# BTT_toolhead_expansion.net
KiCad netlist of a schematic drawn in Altium Designer
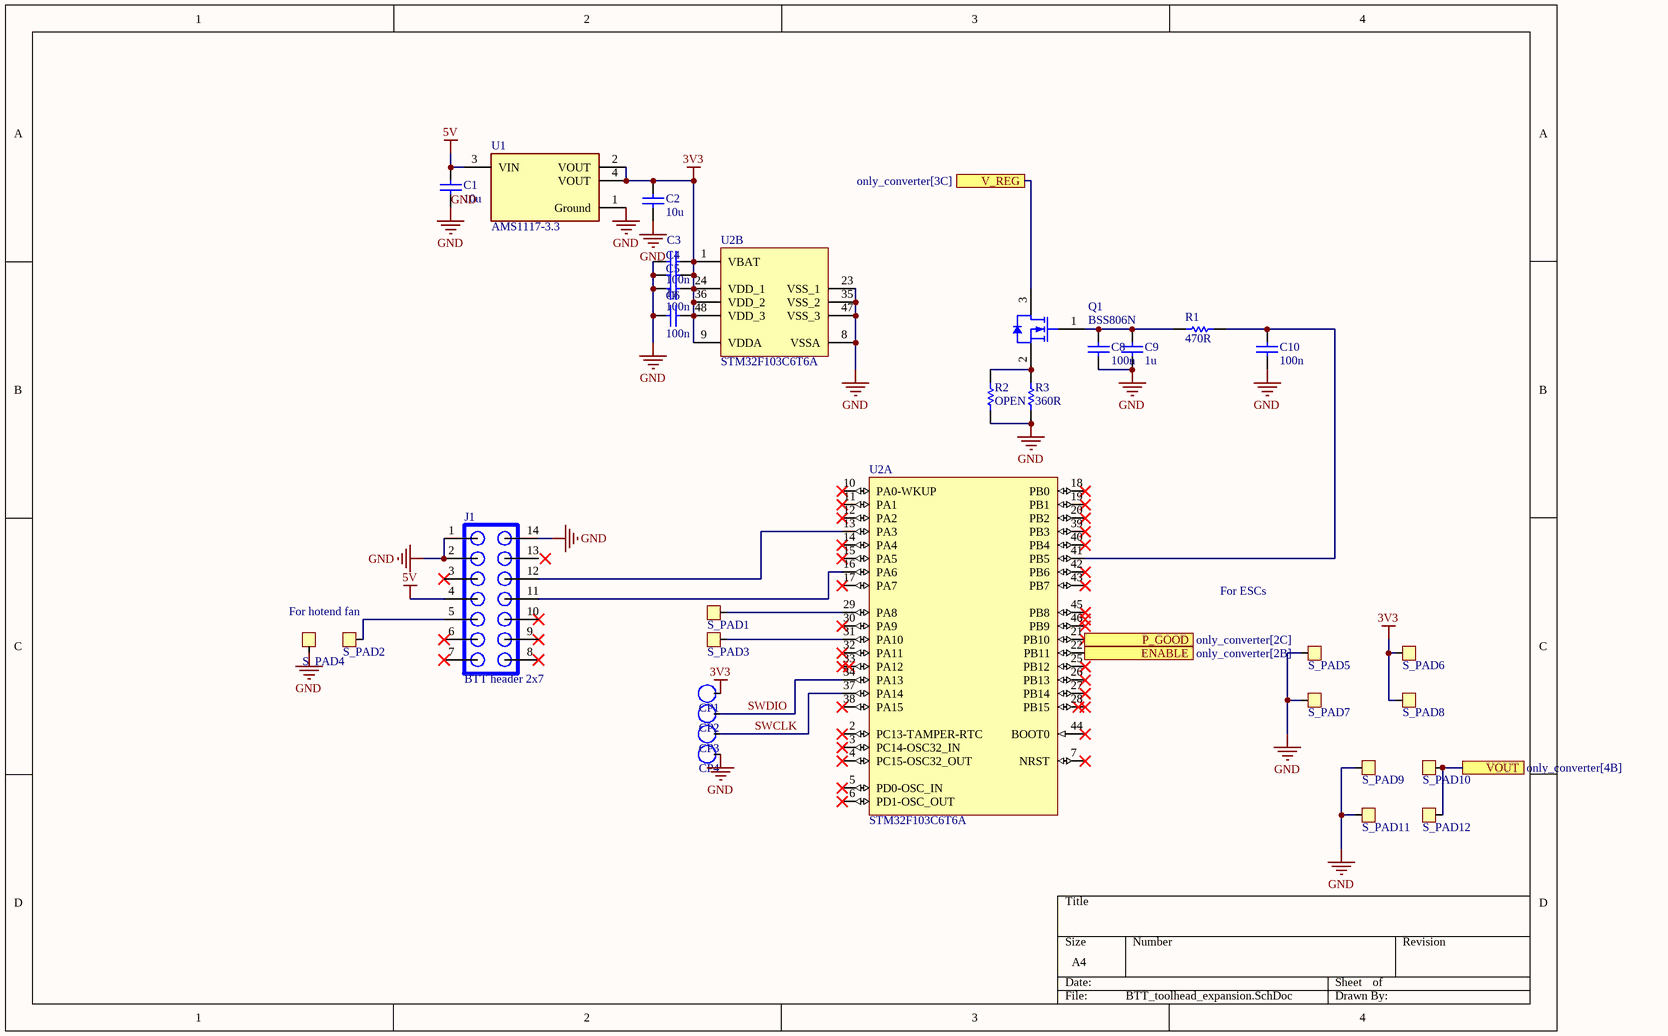
[diagram p0: BTT_toolhead_expansion.SchDoc]

(export (version "E")
  (design (tool "Eeschema 10.0.6"))
  (components
    (comp (ref "C1")
      (value "10u")
      (footprint "CAP FILM 0603_1608")
      (description "Capacitor")
      (libsource (lib "Simulation Generic Components") (part "Capacitor"))
    )
    (comp (ref "C2")
      (value "10u")
      (footprint "CAP FILM 0603_1608")
      (description "Capacitor")
      (libsource (lib "Simulation Generic Components") (part "Capacitor"))
    )
    (comp (ref "C3")
      (value "100n")
      (footprint "CAP FILM 0603_1608")
      (description "Capacitor")
      (libsource (lib "Simulation Generic Components") (part "Capacitor"))
    )
    (comp (ref "C4")
      (value "1p")
      (footprint "CAP FILM 0603_1608")
      (description "Capacitor")
      (libsource (lib "Simulation Generic Components") (part "Capacitor"))
    )
    (comp (ref "C5")
      (value "100n")
      (footprint "CAP FILM 0603_1608")
      (description "Capacitor")
      (libsource (lib "Simulation Generic Components") (part "Capacitor"))
    )
    (comp (ref "C6")
      (value "100n")
      (footprint "CAP FILM 0603_1608")
      (description "Capacitor")
      (libsource (lib "Simulation Generic Components") (part "Capacitor"))
    )
    (comp (ref "C8")
      (value "100n")
      (footprint "CAP FILM 0603_1608")
      (description "Capacitor")
      (libsource (lib "Simulation Generic Components") (part "Capacitor"))
    )
    (comp (ref "C9")
      (value "1u")
      (footprint "CAP FILM 0603_1608")
      (description "Capacitor")
      (libsource (lib "Simulation Generic Components") (part "Capacitor"))
    )
    (comp (ref "C10")
      (value "100n")
      (footprint "CAP FILM 0603_1608")
      (description "Capacitor")
      (libsource (lib "Simulation Generic Components") (part "Capacitor"))
    )
    (comp (ref "CP1")
      (value "CONNECT_PAD")
      (footprint "ROUND_SMALL")
      (libsource (lib "solderpad") (part "CONNECT_PAD"))
    )
    (comp (ref "CP2")
      (value "CONNECT_PAD")
      (footprint "ROUND_SMALL")
      (libsource (lib "solderpad") (part "CONNECT_PAD"))
    )
    (comp (ref "CP3")
      (value "CONNECT_PAD")
      (footprint "ROUND_SMALL")
      (libsource (lib "solderpad") (part "CONNECT_PAD"))
    )
    (comp (ref "CP4")
      (value "CONNECT_PAD")
      (footprint "ROUND_SMALL")
      (libsource (lib "solderpad") (part "CONNECT_PAD"))
    )
    (comp (ref "J1")
      (value "BTT header 2x7")
      (footprint "BTT connector 2x7 THT")
      (libsource (lib "BTT_connector") (part "BTT header 2x7"))
    )
    (comp (ref "Q1")
      (value "BSS806N")
      (footprint "INF-PG-SOT23_M")
      (fields (field (name "MANUFACTURER") "Infineon"))
      (libsource (lib "Altium Content Vault") (part "INF-NEMOS-GSD-3"))
    )
    (comp (ref "R1")
      (value "470R")
      (footprint "RES 0603_1608")
      (description "Resistor")
      (libsource (lib "Simulation Generic Components") (part "Resistor"))
    )
    (comp (ref "R2")
      (value "OPEN")
      (footprint "RES 0603_1608")
      (description "Resistor")
      (libsource (lib "Simulation Generic Components") (part "Resistor"))
    )
    (comp (ref "R3")
      (value "360R")
      (footprint "RES 0603_1608")
      (description "Resistor")
      (libsource (lib "Simulation Generic Components") (part "Resistor"))
    )
    (comp (ref "S_PAD1")
      (value "SOLDER_PAD")
      (footprint "PAD_SQUARE")
      (libsource (lib "solderpad") (part "SOLDER_PAD"))
    )
    (comp (ref "S_PAD2")
      (value "SOLDER_PAD")
      (footprint "PAD_SQUARE")
      (libsource (lib "solderpad") (part "SOLDER_PAD"))
    )
    (comp (ref "S_PAD3")
      (value "SOLDER_PAD")
      (footprint "PAD_SQUARE")
      (libsource (lib "") (part "SOLDER_PAD_3"))
    )
    (comp (ref "S_PAD4")
      (value "SOLDER_PAD")
      (footprint "PAD_SQUARE")
      (libsource (lib "") (part "SOLDER_PAD_2"))
    )
    (comp (ref "S_PAD5")
      (value "SOLDER_PAD")
      (footprint "PAD_SQUARE")
      (libsource (lib "") (part "SOLDER_PAD_1"))
    )
    (comp (ref "S_PAD6")
      (value "SOLDER_PAD")
      (footprint "PAD_SQUARE")
      (libsource (lib "") (part "SOLDER_PAD_1"))
    )
    (comp (ref "S_PAD7")
      (value "SOLDER_PAD")
      (footprint "PAD_SQUARE")
      (libsource (lib "") (part "SOLDER_PAD_1"))
    )
    (comp (ref "S_PAD8")
      (value "SOLDER_PAD")
      (footprint "PAD_SQUARE")
      (libsource (lib "") (part "SOLDER_PAD_1"))
    )
    (comp (ref "S_PAD9")
      (value "SOLDER_PAD")
      (footprint "PAD_SQUARE")
      (libsource (lib "") (part "SOLDER_PAD_1"))
    )
    (comp (ref "S_PAD10")
      (value "SOLDER_PAD")
      (footprint "PAD_SQUARE")
      (libsource (lib "") (part "SOLDER_PAD_3"))
    )
    (comp (ref "S_PAD11")
      (value "SOLDER_PAD")
      (footprint "PAD_SQUARE")
      (libsource (lib "") (part "SOLDER_PAD_1"))
    )
    (comp (ref "S_PAD12")
      (value "SOLDER_PAD")
      (footprint "PAD_SQUARE")
      (libsource (lib "") (part "SOLDER_PAD_3"))
    )
    (comp (ref "U1")
      (value "AMS1117-3.3")
      (footprint "FP-AMS1117-IPC_C")
      (description "LDO Voltage Regulators 1A, 3.3V")
      (fields
        (field (name "OCTOPART") "https://octopart.com/ams1117-3.3-advanced+monolithic+systems-25899300")
        (field (name "MANUFACTURER") "Advanced Monolithic Systems")
      )
      (libsource (lib "Altium Content Vault") (part "8bdbb5f8e77002000e30dd2845d0354"))
    )
    (comp (ref "U2")
      (value "STM32F103C6T6A")
      (footprint "STM-LQFP48_M")
      (libsource (lib "Altium Content Vault") (part "MC-ARM-STM32F103X4_6-SQ48"))
    )
  )
  (nets
    (net (code "1") (name "/ENABLE") (class "Default")
      (node (ref "U2") (pin "22") (pinfunction "PB11_22") (pintype "bidirectional"))
    )
    (net (code "2") (name "/P_GOOD") (class "Default")
      (node (ref "U2") (pin "21") (pinfunction "PB10_21") (pintype "bidirectional+no_connect"))
    )
    (net (code "3") (name "/SWCLK") (class "Default")
      (node (ref "CP3") (pin "1") (pinfunction "1_1") (pintype "passive"))
      (node (ref "U2") (pin "37") (pinfunction "PA14_37") (pintype "bidirectional"))
    )
    (net (code "4") (name "/SWDIO") (class "Default")
      (node (ref "CP2") (pin "1") (pinfunction "1_1") (pintype "passive"))
      (node (ref "U2") (pin "34") (pinfunction "PA13_34") (pintype "bidirectional"))
    )
    (net (code "5") (name "/VOUT") (class "Default")
      (node (ref "S_PAD10") (pin "1") (pinfunction "0_1") (pintype "passive"))
      (node (ref "S_PAD12") (pin "1") (pinfunction "0_1") (pintype "passive"))
    )
    (net (code "6") (name "/V_REG") (class "Default")
      (node (ref "Q1") (pin "3") (pinfunction "DRAIN_3") (pintype "passive"))
    )
    (net (code "7") (name "3V3") (class "Default")
      (node (ref "C2") (pin "2") (pinfunction "2_2") (pintype "passive"))
      (node (ref "C3") (pin "1") (pinfunction "1_1") (pintype "passive"))
      (node (ref "C4") (pin "1") (pinfunction "1_1") (pintype "passive"))
      (node (ref "C5") (pin "1") (pinfunction "1_1") (pintype "passive"))
      (node (ref "C6") (pin "1") (pinfunction "1_1") (pintype "passive"))
      (node (ref "CP1") (pin "1") (pinfunction "1_1") (pintype "passive"))
      (node (ref "S_PAD6") (pin "1") (pinfunction "0_1") (pintype "passive"))
      (node (ref "S_PAD8") (pin "1") (pinfunction "0_1") (pintype "passive"))
      (node (ref "U1") (pin "2") (pinfunction "VOUT_2") (pintype "passive"))
      (node (ref "U1") (pin "4") (pinfunction "VOUT_4") (pintype "passive"))
      (node (ref "U2") (pin "1") (pinfunction "VBAT_1") (pintype "power_in"))
      (node (ref "U2") (pin "24") (pinfunction "VDD_1_24") (pintype "power_in"))
      (node (ref "U2") (pin "36") (pinfunction "VDD_2_36") (pintype "power_in"))
      (node (ref "U2") (pin "48") (pinfunction "VDD_3_48") (pintype "power_in"))
      (node (ref "U2") (pin "9") (pinfunction "VDDA_9") (pintype "power_in"))
    )
    (net (code "8") (name "5V") (class "Default")
      (node (ref "C1") (pin "2") (pinfunction "2_2") (pintype "passive"))
      (node (ref "J1") (pin "4") (pinfunction "4_4") (pintype "passive"))
      (node (ref "U1") (pin "3") (pinfunction "VIN_3") (pintype "power_in"))
    )
    (net (code "9") (name "GND") (class "Default")
      (node (ref "C1") (pin "1") (pinfunction "1_1") (pintype "passive"))
      (node (ref "C10") (pin "1") (pinfunction "1_1") (pintype "passive"))
      (node (ref "C2") (pin "1") (pinfunction "1_1") (pintype "passive"))
      (node (ref "C3") (pin "2") (pinfunction "2_2") (pintype "passive"))
      (node (ref "C4") (pin "2") (pinfunction "2_2") (pintype "passive"))
      (node (ref "C5") (pin "2") (pinfunction "2_2") (pintype "passive"))
      (node (ref "C6") (pin "2") (pinfunction "2_2") (pintype "passive"))
      (node (ref "C8") (pin "1") (pinfunction "1_1") (pintype "passive"))
      (node (ref "C9") (pin "1") (pinfunction "1_1") (pintype "passive"))
      (node (ref "CP4") (pin "1") (pinfunction "1_1") (pintype "passive"))
      (node (ref "J1") (pin "1") (pinfunction "1_1") (pintype "passive"))
      (node (ref "J1") (pin "14") (pinfunction "14_14") (pintype "passive"))
      (node (ref "J1") (pin "2") (pinfunction "2_2") (pintype "passive"))
      (node (ref "R2") (pin "1") (pinfunction "1_1") (pintype "passive"))
      (node (ref "R3") (pin "1") (pinfunction "1_1") (pintype "passive"))
      (node (ref "S_PAD11") (pin "1") (pinfunction "0_1") (pintype "passive"))
      (node (ref "S_PAD4") (pin "1") (pinfunction "0_1") (pintype "passive"))
      (node (ref "S_PAD5") (pin "1") (pinfunction "0_1") (pintype "passive"))
      (node (ref "S_PAD7") (pin "1") (pinfunction "0_1") (pintype "passive"))
      (node (ref "S_PAD9") (pin "1") (pinfunction "0_1") (pintype "passive"))
      (node (ref "U1") (pin "1") (pinfunction "Ground_1") (pintype "power_in"))
      (node (ref "U2") (pin "23") (pinfunction "VSS_1_23") (pintype "power_in"))
      (node (ref "U2") (pin "35") (pinfunction "VSS_2_35") (pintype "power_in"))
      (node (ref "U2") (pin "47") (pinfunction "VSS_3_47") (pintype "power_in"))
      (node (ref "U2") (pin "8") (pinfunction "VSSA_8") (pintype "power_in"))
    )
    (net (code "10") (name "Net-(Q1-GATE)") (class "Default")
      (node (ref "C8") (pin "2") (pinfunction "2_2") (pintype "passive"))
      (node (ref "C9") (pin "2") (pinfunction "2_2") (pintype "passive"))
      (node (ref "Q1") (pin "1") (pinfunction "GATE_1") (pintype "passive"))
      (node (ref "R1") (pin "1") (pinfunction "1_1") (pintype "passive"))
    )
    (net (code "11") (name "Net-(Q1-SOURCE)") (class "Default")
      (node (ref "Q1") (pin "2") (pinfunction "SOURCE_2") (pintype "passive"))
      (node (ref "R2") (pin "2") (pinfunction "2_2") (pintype "passive"))
      (node (ref "R3") (pin "2") (pinfunction "2_2") (pintype "passive"))
    )
    (net (code "12") (name "Net-(S_PAD1-0)") (class "Default")
      (node (ref "S_PAD1") (pin "1") (pinfunction "0_1") (pintype "passive"))
      (node (ref "U2") (pin "29") (pinfunction "PA8_29") (pintype "bidirectional"))
    )
    (net (code "13") (name "Net-(S_PAD2-0)") (class "Default")
      (node (ref "J1") (pin "5") (pinfunction "5_5") (pintype "passive"))
      (node (ref "S_PAD2") (pin "1") (pinfunction "0_1") (pintype "passive"))
    )
    (net (code "14") (name "Net-(S_PAD3-0)") (class "Default")
      (node (ref "S_PAD3") (pin "1") (pinfunction "0_1") (pintype "passive"))
      (node (ref "U2") (pin "31") (pinfunction "PA10_31") (pintype "bidirectional"))
    )
    (net (code "15") (name "Net-(U2A-PA3)") (class "Default")
      (node (ref "J1") (pin "12") (pinfunction "12_12") (pintype "passive"))
      (node (ref "U2") (pin "13") (pinfunction "PA3_13") (pintype "bidirectional"))
    )
    (net (code "16") (name "Net-(U2A-PA6)") (class "Default")
      (node (ref "J1") (pin "11") (pinfunction "11_11") (pintype "passive"))
      (node (ref "U2") (pin "16") (pinfunction "PA6_16") (pintype "bidirectional"))
    )
    (net (code "17") (name "Net-(U2A-PB5)") (class "Default")
      (node (ref "C10") (pin "2") (pinfunction "2_2") (pintype "passive"))
      (node (ref "R1") (pin "2") (pinfunction "2_2") (pintype "passive"))
      (node (ref "U2") (pin "41") (pinfunction "PB5_41") (pintype "bidirectional"))
    )
    (net (code "18") (name "unconnected-(J1-Pad3)") (class "Default")
      (node (ref "J1") (pin "3") (pinfunction "3_3") (pintype "passive+no_connect"))
    )
    (net (code "19") (name "unconnected-(J1-Pad6)") (class "Default")
      (node (ref "J1") (pin "6") (pinfunction "6_6") (pintype "passive+no_connect"))
    )
    (net (code "20") (name "unconnected-(J1-Pad7)") (class "Default")
      (node (ref "J1") (pin "7") (pinfunction "7_7") (pintype "passive+no_connect"))
    )
    (net (code "21") (name "unconnected-(J1-Pad8)") (class "Default")
      (node (ref "J1") (pin "8") (pinfunction "8_8") (pintype "passive+no_connect"))
    )
    (net (code "22") (name "unconnected-(J1-Pad9)") (class "Default")
      (node (ref "J1") (pin "9") (pinfunction "9_9") (pintype "passive+no_connect"))
    )
    (net (code "23") (name "unconnected-(J1-Pad10)") (class "Default")
      (node (ref "J1") (pin "10") (pinfunction "10_10") (pintype "passive+no_connect"))
    )
    (net (code "24") (name "unconnected-(J1-Pad13)") (class "Default")
      (node (ref "J1") (pin "13") (pinfunction "13_13") (pintype "passive"))
    )
    (net (code "25") (name "unconnected-(U2A-BOOT0-Pad44)") (class "Default")
      (node (ref "U2") (pin "44") (pinfunction "BOOT0_44") (pintype "input+no_connect"))
    )
    (net (code "26") (name "unconnected-(U2A-NRST-Pad7)") (class "Default")
      (node (ref "U2") (pin "7") (pinfunction "NRST_7") (pintype "bidirectional+no_connect"))
    )
    (net (code "27") (name "unconnected-(U2A-PA0-WKUP-Pad10)") (class "Default")
      (node (ref "U2") (pin "10") (pinfunction "PA0-WKUP_10") (pintype "bidirectional+no_connect"))
    )
    (net (code "28") (name "unconnected-(U2A-PA1-Pad11)") (class "Default")
      (node (ref "U2") (pin "11") (pinfunction "PA1_11") (pintype "bidirectional+no_connect"))
    )
    (net (code "29") (name "unconnected-(U2A-PA2-Pad12)") (class "Default")
      (node (ref "U2") (pin "12") (pinfunction "PA2_12") (pintype "bidirectional+no_connect"))
    )
    (net (code "30") (name "unconnected-(U2A-PA4-Pad14)") (class "Default")
      (node (ref "U2") (pin "14") (pinfunction "PA4_14") (pintype "bidirectional+no_connect"))
    )
    (net (code "31") (name "unconnected-(U2A-PA5-Pad15)") (class "Default")
      (node (ref "U2") (pin "15") (pinfunction "PA5_15") (pintype "bidirectional+no_connect"))
    )
    (net (code "32") (name "unconnected-(U2A-PA7-Pad17)") (class "Default")
      (node (ref "U2") (pin "17") (pinfunction "PA7_17") (pintype "bidirectional+no_connect"))
    )
    (net (code "33") (name "unconnected-(U2A-PA9-Pad30)") (class "Default")
      (node (ref "U2") (pin "30") (pinfunction "PA9_30") (pintype "bidirectional+no_connect"))
    )
    (net (code "34") (name "unconnected-(U2A-PA11-Pad32)") (class "Default")
      (node (ref "U2") (pin "32") (pinfunction "PA11_32") (pintype "bidirectional+no_connect"))
    )
    (net (code "35") (name "unconnected-(U2A-PA12-Pad33)") (class "Default")
      (node (ref "U2") (pin "33") (pinfunction "PA12_33") (pintype "bidirectional+no_connect"))
    )
    (net (code "36") (name "unconnected-(U2A-PA15-Pad38)") (class "Default")
      (node (ref "U2") (pin "38") (pinfunction "PA15_38") (pintype "bidirectional+no_connect"))
    )
    (net (code "37") (name "unconnected-(U2A-PB0-Pad18)") (class "Default")
      (node (ref "U2") (pin "18") (pinfunction "PB0_18") (pintype "bidirectional+no_connect"))
    )
    (net (code "38") (name "unconnected-(U2A-PB1-Pad19)") (class "Default")
      (node (ref "U2") (pin "19") (pinfunction "PB1_19") (pintype "bidirectional+no_connect"))
    )
    (net (code "39") (name "unconnected-(U2A-PB2-Pad20)") (class "Default")
      (node (ref "U2") (pin "20") (pinfunction "PB2_20") (pintype "bidirectional+no_connect"))
    )
    (net (code "40") (name "unconnected-(U2A-PB3-Pad39)") (class "Default")
      (node (ref "U2") (pin "39") (pinfunction "PB3_39") (pintype "bidirectional+no_connect"))
    )
    (net (code "41") (name "unconnected-(U2A-PB4-Pad40)") (class "Default")
      (node (ref "U2") (pin "40") (pinfunction "PB4_40") (pintype "bidirectional+no_connect"))
    )
    (net (code "42") (name "unconnected-(U2A-PB6-Pad42)") (class "Default")
      (node (ref "U2") (pin "42") (pinfunction "PB6_42") (pintype "bidirectional+no_connect"))
    )
    (net (code "43") (name "unconnected-(U2A-PB7-Pad43)") (class "Default")
      (node (ref "U2") (pin "43") (pinfunction "PB7_43") (pintype "bidirectional+no_connect"))
    )
    (net (code "44") (name "unconnected-(U2A-PB8-Pad45)") (class "Default")
      (node (ref "U2") (pin "45") (pinfunction "PB8_45") (pintype "bidirectional+no_connect"))
    )
    (net (code "45") (name "unconnected-(U2A-PB9-Pad46)") (class "Default")
      (node (ref "U2") (pin "46") (pinfunction "PB9_46") (pintype "bidirectional+no_connect"))
    )
    (net (code "46") (name "unconnected-(U2A-PB12-Pad25)") (class "Default")
      (node (ref "U2") (pin "25") (pinfunction "PB12_25") (pintype "bidirectional+no_connect"))
    )
    (net (code "47") (name "unconnected-(U2A-PB13-Pad26)") (class "Default")
      (node (ref "U2") (pin "26") (pinfunction "PB13_26") (pintype "bidirectional+no_connect"))
    )
    (net (code "48") (name "unconnected-(U2A-PB14-Pad27)") (class "Default")
      (node (ref "U2") (pin "27") (pinfunction "PB14_27") (pintype "bidirectional+no_connect"))
    )
    (net (code "49") (name "unconnected-(U2A-PB15-Pad28)") (class "Default")
      (node (ref "U2") (pin "28") (pinfunction "PB15_28") (pintype "bidirectional+no_connect"))
    )
    (net (code "50") (name "unconnected-(U2A-PC13-TAMPER-RTC-Pad2)") (class "Default")
      (node (ref "U2") (pin "2") (pinfunction "PC13-TAMPER-RTC_2") (pintype "bidirectional+no_connect"))
    )
    (net (code "51") (name "unconnected-(U2A-PC14-OSC32_IN-Pad3)") (class "Default")
      (node (ref "U2") (pin "3") (pinfunction "PC14-OSC32_IN_3") (pintype "bidirectional+no_connect"))
    )
    (net (code "52") (name "unconnected-(U2A-PC15-OSC32_OUT-Pad4)") (class "Default")
      (node (ref "U2") (pin "4") (pinfunction "PC15-OSC32_OUT_4") (pintype "bidirectional+no_connect"))
    )
    (net (code "53") (name "unconnected-(U2A-PD0-OSC_IN-Pad5)") (class "Default")
      (node (ref "U2") (pin "5") (pinfunction "PD0-OSC_IN_5") (pintype "bidirectional+no_connect"))
    )
    (net (code "54") (name "unconnected-(U2A-PD1-OSC_OUT-Pad6)") (class "Default")
      (node (ref "U2") (pin "6") (pinfunction "PD1-OSC_OUT_6") (pintype "bidirectional+no_connect"))
    )
  )
)
